# tcrt5000_schematic.net
KiCad netlist of a schematic drawn in Altium Designer
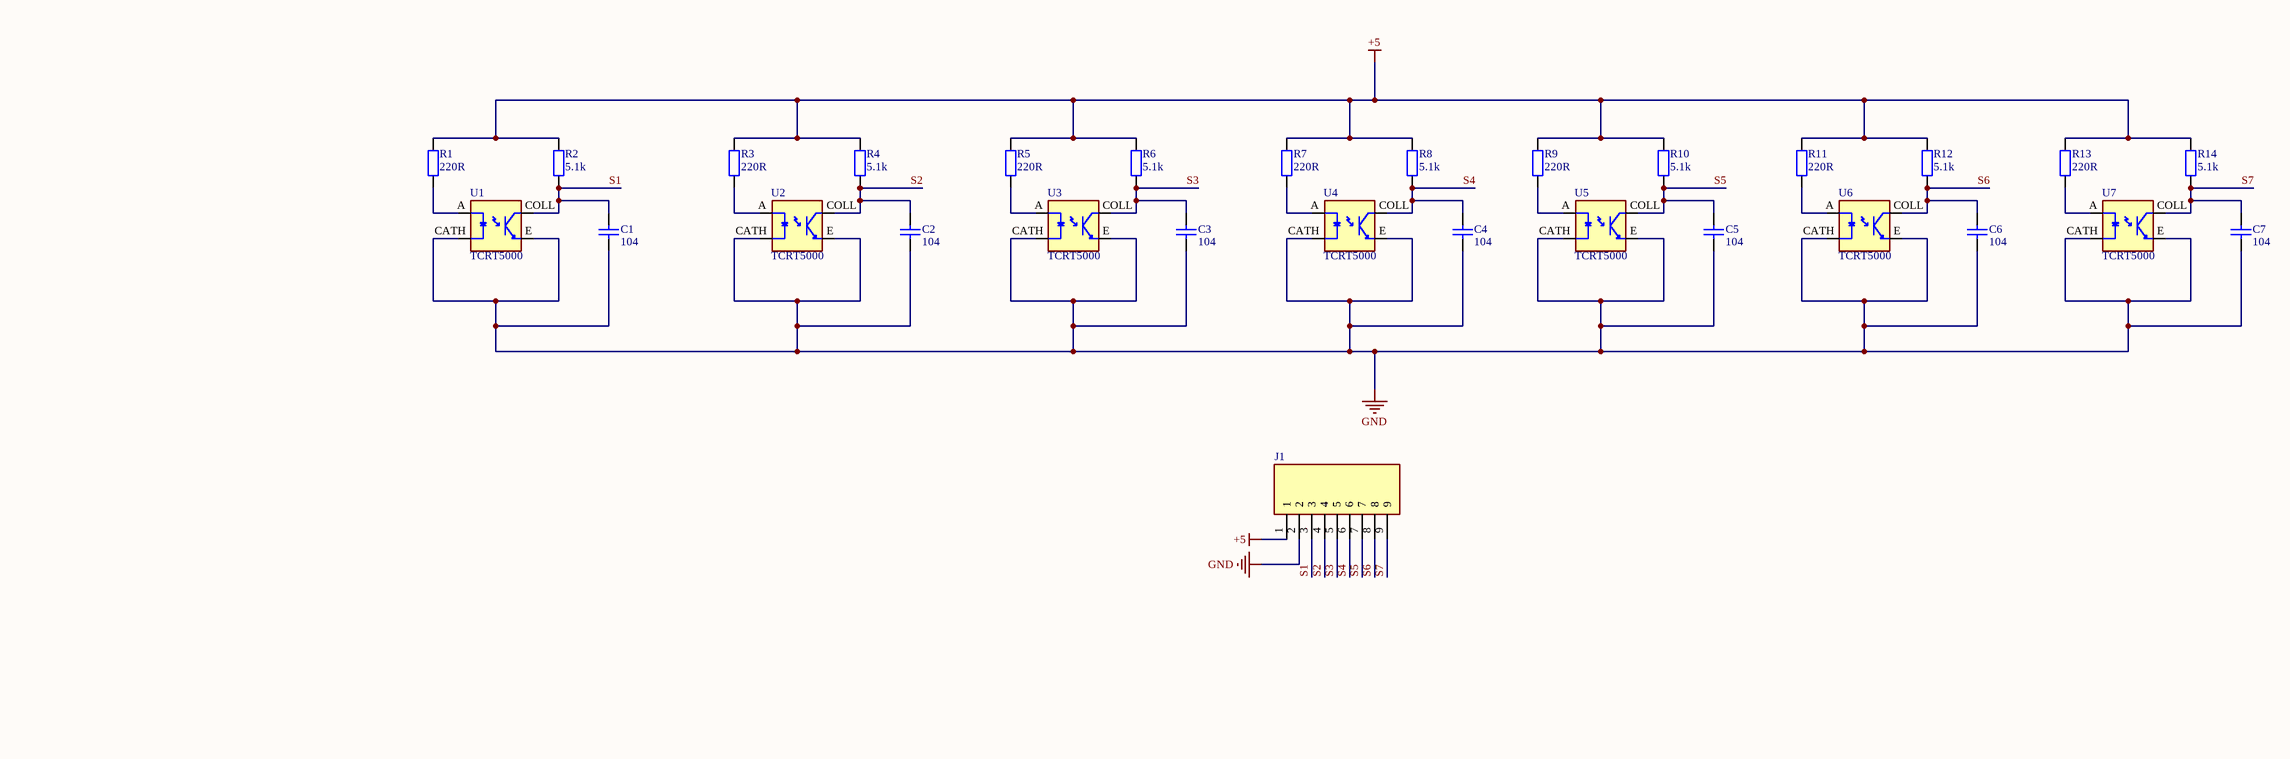
[diagram p0: tcrt5000_schematic.SchDoc]

(export (version "E")
  (design (tool "Eeschema 10.0.6"))
  (components
    (comp (ref "C1")
      (value "104")
      (footprint "tu 1206")
      (description "Dán")
      (libsource (lib "Capacitor") (part "Tu 1206 104 50V 20%"))
    )
    (comp (ref "C2")
      (value "104")
      (footprint "tu 1206")
      (description "Dán")
      (libsource (lib "Capacitor") (part "Tu 1206 104 50V 20%"))
    )
    (comp (ref "C3")
      (value "104")
      (footprint "tu 1206")
      (description "Dán")
      (libsource (lib "Capacitor") (part "Tu 1206 104 50V 20%"))
    )
    (comp (ref "C4")
      (value "104")
      (footprint "tu 1206")
      (description "Dán")
      (libsource (lib "Capacitor") (part "Tu 1206 104 50V 20%"))
    )
    (comp (ref "C5")
      (value "104")
      (footprint "tu 1206")
      (description "Dán")
      (libsource (lib "Capacitor") (part "Tu 1206 104 50V 20%"))
    )
    (comp (ref "C6")
      (value "104")
      (footprint "tu 1206")
      (description "Dán")
      (libsource (lib "Capacitor") (part "Tu 1206 104 50V 20%"))
    )
    (comp (ref "C7")
      (value "104")
      (footprint "tu 1206")
      (description "Dán")
      (libsource (lib "Capacitor") (part "Tu 1206 104 50V 20%"))
    )
    (comp (ref "J1")
      (value "440052-9")
      (footprint "TE_440052-9")
      (libsource (lib "440052-9") (part "440052-9"))
    )
    (comp (ref "R1")
      (value "220R")
      (footprint "tro smd 1206")
      (description "Dán")
      (libsource (lib "Resistor") (part "Tro 1206 5% 220R"))
    )
    (comp (ref "R2")
      (value "5.1k")
      (footprint "tro smd 1206")
      (description "Dán")
      (libsource (lib "Resistor") (part "Tro 1206 1% 5.1k"))
    )
    (comp (ref "R3")
      (value "220R")
      (footprint "tro smd 1206")
      (description "Dán")
      (libsource (lib "Resistor") (part "Tro 1206 5% 220R"))
    )
    (comp (ref "R4")
      (value "5.1k")
      (footprint "tro smd 1206")
      (description "Dán")
      (libsource (lib "Resistor") (part "Tro 1206 1% 5.1k"))
    )
    (comp (ref "R5")
      (value "220R")
      (footprint "tro smd 1206")
      (description "Dán")
      (libsource (lib "Resistor") (part "Tro 1206 5% 220R"))
    )
    (comp (ref "R6")
      (value "5.1k")
      (footprint "tro smd 1206")
      (description "Dán")
      (libsource (lib "Resistor") (part "Tro 1206 1% 5.1k"))
    )
    (comp (ref "R7")
      (value "220R")
      (footprint "tro smd 1206")
      (description "Dán")
      (libsource (lib "Resistor") (part "Tro 1206 5% 220R"))
    )
    (comp (ref "R8")
      (value "5.1k")
      (footprint "tro smd 1206")
      (description "Dán")
      (libsource (lib "Resistor") (part "Tro 1206 1% 5.1k"))
    )
    (comp (ref "R9")
      (value "220R")
      (footprint "tro smd 1206")
      (description "Dán")
      (libsource (lib "Resistor") (part "Tro 1206 5% 220R"))
    )
    (comp (ref "R10")
      (value "5.1k")
      (footprint "tro smd 1206")
      (description "Dán")
      (libsource (lib "Resistor") (part "Tro 1206 1% 5.1k"))
    )
    (comp (ref "R11")
      (value "220R")
      (footprint "tro smd 1206")
      (description "Dán")
      (libsource (lib "Resistor") (part "Tro 1206 5% 220R"))
    )
    (comp (ref "R12")
      (value "5.1k")
      (footprint "tro smd 1206")
      (description "Dán")
      (libsource (lib "Resistor") (part "Tro 1206 1% 5.1k"))
    )
    (comp (ref "R13")
      (value "220R")
      (footprint "tro smd 1206")
      (description "Dán")
      (libsource (lib "Resistor") (part "Tro 1206 5% 220R"))
    )
    (comp (ref "R14")
      (value "5.1k")
      (footprint "tro smd 1206")
      (description "Dán")
      (libsource (lib "Resistor") (part "Tro 1206 1% 5.1k"))
    )
    (comp (ref "U1")
      (value "TCRT5000")
      (footprint "OPTO_TCRT5000")
      (description "950 nm 60 mA Through Hole Reflective Optical Sensor with Transistor Output")
      (libsource (lib "TCRT5000") (part "TCRT5000"))
    )
    (comp (ref "U2")
      (value "TCRT5000")
      (footprint "OPTO_TCRT5000")
      (description "950 nm 60 mA Through Hole Reflective Optical Sensor with Transistor Output")
      (libsource (lib "TCRT5000") (part "TCRT5000"))
    )
    (comp (ref "U3")
      (value "TCRT5000")
      (footprint "OPTO_TCRT5000")
      (description "950 nm 60 mA Through Hole Reflective Optical Sensor with Transistor Output")
      (libsource (lib "TCRT5000") (part "TCRT5000"))
    )
    (comp (ref "U4")
      (value "TCRT5000")
      (footprint "OPTO_TCRT5000")
      (description "950 nm 60 mA Through Hole Reflective Optical Sensor with Transistor Output")
      (libsource (lib "TCRT5000") (part "TCRT5000"))
    )
    (comp (ref "U5")
      (value "TCRT5000")
      (footprint "OPTO_TCRT5000")
      (description "950 nm 60 mA Through Hole Reflective Optical Sensor with Transistor Output")
      (libsource (lib "TCRT5000") (part "TCRT5000"))
    )
    (comp (ref "U6")
      (value "TCRT5000")
      (footprint "OPTO_TCRT5000")
      (description "950 nm 60 mA Through Hole Reflective Optical Sensor with Transistor Output")
      (libsource (lib "TCRT5000") (part "TCRT5000"))
    )
    (comp (ref "U7")
      (value "TCRT5000")
      (footprint "OPTO_TCRT5000")
      (description "950 nm 60 mA Through Hole Reflective Optical Sensor with Transistor Output")
      (libsource (lib "TCRT5000") (part "TCRT5000"))
    )
  )
  (nets
    (net (code "1") (name "+5") (class "Default")
      (node (ref "J1") (pin "1") (pinfunction "1_1") (pintype "passive"))
      (node (ref "R1") (pin "2") (pinfunction "2_2") (pintype "passive"))
      (node (ref "R10") (pin "2") (pinfunction "2_2") (pintype "passive"))
      (node (ref "R11") (pin "2") (pinfunction "2_2") (pintype "passive"))
      (node (ref "R12") (pin "2") (pinfunction "2_2") (pintype "passive"))
      (node (ref "R13") (pin "2") (pinfunction "2_2") (pintype "passive"))
      (node (ref "R14") (pin "2") (pinfunction "2_2") (pintype "passive"))
      (node (ref "R2") (pin "2") (pinfunction "2_2") (pintype "passive"))
      (node (ref "R3") (pin "2") (pinfunction "2_2") (pintype "passive"))
      (node (ref "R4") (pin "2") (pinfunction "2_2") (pintype "passive"))
      (node (ref "R5") (pin "2") (pinfunction "2_2") (pintype "passive"))
      (node (ref "R6") (pin "2") (pinfunction "2_2") (pintype "passive"))
      (node (ref "R7") (pin "2") (pinfunction "2_2") (pintype "passive"))
      (node (ref "R8") (pin "2") (pinfunction "2_2") (pintype "passive"))
      (node (ref "R9") (pin "2") (pinfunction "2_2") (pintype "passive"))
    )
    (net (code "2") (name "/S1") (class "Default")
      (node (ref "C1") (pin "1") (pinfunction "1_1") (pintype "passive"))
      (node (ref "J1") (pin "3") (pinfunction "3_3") (pintype "passive"))
      (node (ref "R2") (pin "1") (pinfunction "1_1") (pintype "passive"))
      (node (ref "U1") (pin "COLL") (pinfunction "COLL_COLL") (pintype "passive"))
    )
    (net (code "3") (name "/S2") (class "Default")
      (node (ref "C2") (pin "1") (pinfunction "1_1") (pintype "passive"))
      (node (ref "J1") (pin "4") (pinfunction "4_4") (pintype "passive"))
      (node (ref "R4") (pin "1") (pinfunction "1_1") (pintype "passive"))
      (node (ref "U2") (pin "COLL") (pinfunction "COLL_COLL") (pintype "passive"))
    )
    (net (code "4") (name "/S3") (class "Default")
      (node (ref "C3") (pin "1") (pinfunction "1_1") (pintype "passive"))
      (node (ref "J1") (pin "5") (pinfunction "5_5") (pintype "passive"))
      (node (ref "R6") (pin "1") (pinfunction "1_1") (pintype "passive"))
      (node (ref "U3") (pin "COLL") (pinfunction "COLL_COLL") (pintype "passive"))
    )
    (net (code "5") (name "/S4") (class "Default")
      (node (ref "C4") (pin "1") (pinfunction "1_1") (pintype "passive"))
      (node (ref "J1") (pin "6") (pinfunction "6_6") (pintype "passive"))
      (node (ref "R8") (pin "1") (pinfunction "1_1") (pintype "passive"))
      (node (ref "U4") (pin "COLL") (pinfunction "COLL_COLL") (pintype "passive"))
    )
    (net (code "6") (name "/S5") (class "Default")
      (node (ref "C5") (pin "1") (pinfunction "1_1") (pintype "passive"))
      (node (ref "J1") (pin "7") (pinfunction "7_7") (pintype "passive"))
      (node (ref "R10") (pin "1") (pinfunction "1_1") (pintype "passive"))
      (node (ref "U5") (pin "COLL") (pinfunction "COLL_COLL") (pintype "passive"))
    )
    (net (code "7") (name "/S6") (class "Default")
      (node (ref "C6") (pin "1") (pinfunction "1_1") (pintype "passive"))
      (node (ref "J1") (pin "8") (pinfunction "8_8") (pintype "passive"))
      (node (ref "R12") (pin "1") (pinfunction "1_1") (pintype "passive"))
      (node (ref "U6") (pin "COLL") (pinfunction "COLL_COLL") (pintype "passive"))
    )
    (net (code "8") (name "/S7") (class "Default")
      (node (ref "C7") (pin "1") (pinfunction "1_1") (pintype "passive"))
      (node (ref "J1") (pin "9") (pinfunction "9_9") (pintype "passive"))
      (node (ref "R14") (pin "1") (pinfunction "1_1") (pintype "passive"))
      (node (ref "U7") (pin "COLL") (pinfunction "COLL_COLL") (pintype "passive"))
    )
    (net (code "9") (name "GND") (class "Default")
      (node (ref "C1") (pin "2") (pinfunction "2_2") (pintype "passive"))
      (node (ref "C2") (pin "2") (pinfunction "2_2") (pintype "passive"))
      (node (ref "C3") (pin "2") (pinfunction "2_2") (pintype "passive"))
      (node (ref "C4") (pin "2") (pinfunction "2_2") (pintype "passive"))
      (node (ref "C5") (pin "2") (pinfunction "2_2") (pintype "passive"))
      (node (ref "C6") (pin "2") (pinfunction "2_2") (pintype "passive"))
      (node (ref "C7") (pin "2") (pinfunction "2_2") (pintype "passive"))
      (node (ref "J1") (pin "2") (pinfunction "2_2") (pintype "passive"))
      (node (ref "U1") (pin "CATH") (pinfunction "CATH_CATH") (pintype "passive"))
      (node (ref "U1") (pin "E") (pinfunction "E_E") (pintype "passive"))
      (node (ref "U2") (pin "CATH") (pinfunction "CATH_CATH") (pintype "passive"))
      (node (ref "U2") (pin "E") (pinfunction "E_E") (pintype "passive"))
      (node (ref "U3") (pin "CATH") (pinfunction "CATH_CATH") (pintype "passive"))
      (node (ref "U3") (pin "E") (pinfunction "E_E") (pintype "passive"))
      (node (ref "U4") (pin "CATH") (pinfunction "CATH_CATH") (pintype "passive"))
      (node (ref "U4") (pin "E") (pinfunction "E_E") (pintype "passive"))
      (node (ref "U5") (pin "CATH") (pinfunction "CATH_CATH") (pintype "passive"))
      (node (ref "U5") (pin "E") (pinfunction "E_E") (pintype "passive"))
      (node (ref "U6") (pin "CATH") (pinfunction "CATH_CATH") (pintype "passive"))
      (node (ref "U6") (pin "E") (pinfunction "E_E") (pintype "passive"))
      (node (ref "U7") (pin "CATH") (pinfunction "CATH_CATH") (pintype "passive"))
      (node (ref "U7") (pin "E") (pinfunction "E_E") (pintype "passive"))
    )
    (net (code "10") (name "Net-(R1-Pad1)") (class "Default")
      (node (ref "R1") (pin "1") (pinfunction "1_1") (pintype "passive"))
      (node (ref "U1") (pin "A") (pinfunction "A_A") (pintype "passive"))
    )
    (net (code "11") (name "Net-(R3-Pad1)") (class "Default")
      (node (ref "R3") (pin "1") (pinfunction "1_1") (pintype "passive"))
      (node (ref "U2") (pin "A") (pinfunction "A_A") (pintype "passive"))
    )
    (net (code "12") (name "Net-(R5-Pad1)") (class "Default")
      (node (ref "R5") (pin "1") (pinfunction "1_1") (pintype "passive"))
      (node (ref "U3") (pin "A") (pinfunction "A_A") (pintype "passive"))
    )
    (net (code "13") (name "Net-(R7-Pad1)") (class "Default")
      (node (ref "R7") (pin "1") (pinfunction "1_1") (pintype "passive"))
      (node (ref "U4") (pin "A") (pinfunction "A_A") (pintype "passive"))
    )
    (net (code "14") (name "Net-(R9-Pad1)") (class "Default")
      (node (ref "R9") (pin "1") (pinfunction "1_1") (pintype "passive"))
      (node (ref "U5") (pin "A") (pinfunction "A_A") (pintype "passive"))
    )
    (net (code "15") (name "Net-(R11-Pad1)") (class "Default")
      (node (ref "R11") (pin "1") (pinfunction "1_1") (pintype "passive"))
      (node (ref "U6") (pin "A") (pinfunction "A_A") (pintype "passive"))
    )
    (net (code "16") (name "Net-(R13-Pad1)") (class "Default")
      (node (ref "R13") (pin "1") (pinfunction "1_1") (pintype "passive"))
      (node (ref "U7") (pin "A") (pinfunction "A_A") (pintype "passive"))
    )
  )
)
